# Mood-Badge.net
KiCad netlist of a schematic drawn in EAGLE
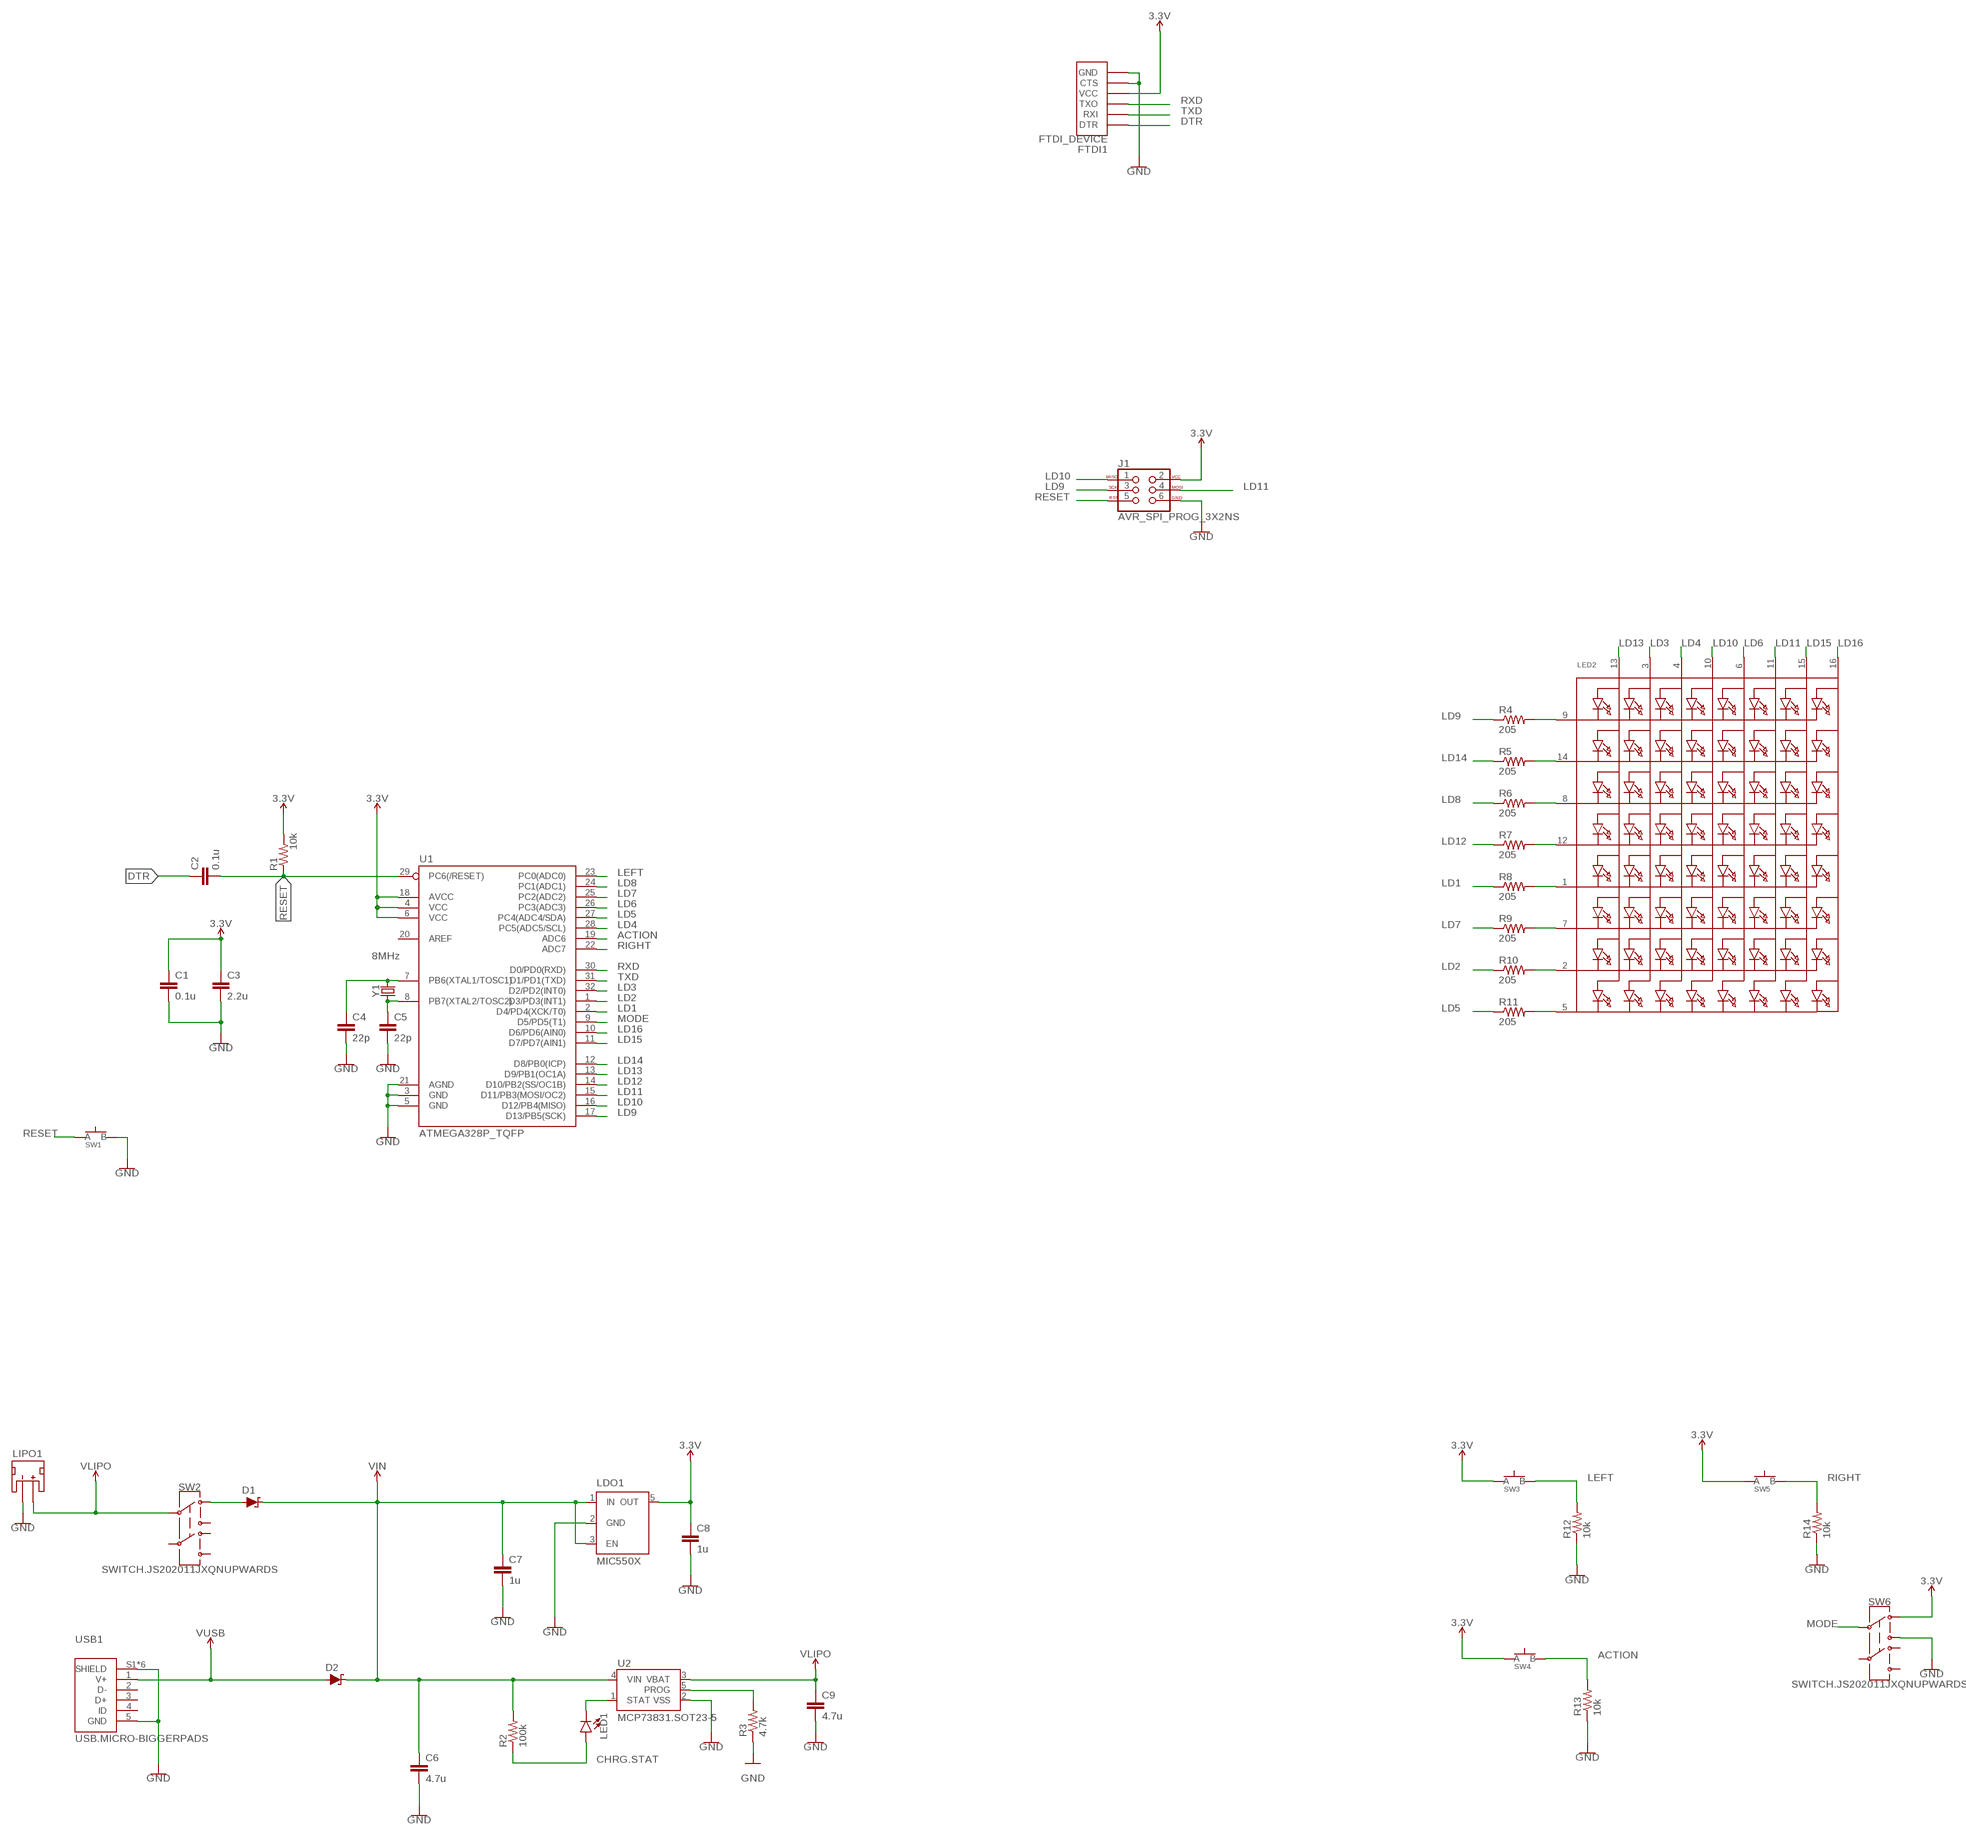
[diagram p0: schematic, sheet 1]

(export (version "E")
  (design (tool "Eeschema 10.0.6"))
  (components
    (comp (ref "C1")
      (value "0.1u")
      (footprint "eagle-import:C0603")
      (libsource (lib "eagle-import") (part "CAPACITOR0603"))
    )
    (comp (ref "C2")
      (value "0.1u")
      (footprint "eagle-import:C0603")
      (libsource (lib "eagle-import") (part "CAPACITOR0603"))
    )
    (comp (ref "C3")
      (value "2.2u")
      (footprint "eagle-import:C0603")
      (libsource (lib "eagle-import") (part "CAPACITOR0603"))
    )
    (comp (ref "C4")
      (value "22p")
      (footprint "eagle-import:C0603")
      (libsource (lib "eagle-import") (part "CAPACITOR0603"))
    )
    (comp (ref "C5")
      (value "22p")
      (footprint "eagle-import:C0603")
      (libsource (lib "eagle-import") (part "CAPACITOR0603"))
    )
    (comp (ref "C6")
      (value "4.7u")
      (footprint "eagle-import:C0603")
      (libsource (lib "eagle-import") (part "CAPACITOR0603"))
    )
    (comp (ref "C7")
      (value "1u")
      (footprint "eagle-import:C0603")
      (libsource (lib "eagle-import") (part "CAPACITOR0603"))
    )
    (comp (ref "C8")
      (value "1u")
      (footprint "eagle-import:C0603")
      (libsource (lib "eagle-import") (part "CAPACITOR0603"))
    )
    (comp (ref "C9")
      (value "4.7u")
      (footprint "eagle-import:C0603")
      (libsource (lib "eagle-import") (part "CAPACITOR0603"))
    )
    (comp (ref "D1")
      (value "SCHOTTKY-USC")
      (footprint "eagle-import:USC")
      (libsource (lib "eagle-import") (part "SCHOTTKY-USC"))
    )
    (comp (ref "D2")
      (value "SCHOTTKY-USC")
      (footprint "eagle-import:USC")
      (libsource (lib "eagle-import") (part "SCHOTTKY-USC"))
    )
    (comp (ref "FTDI1")
      (value "FTDI_DEVICE")
      (footprint "eagle-import:FTDI_DEVICE")
      (libsource (lib "eagle-import") (part "FTDI_DEVICE"))
    )
    (comp (ref "J1")
      (value "AVR_SPI_PROG_3X2NS")
      (footprint "eagle-import:2X3-NS")
      (libsource (lib "eagle-import") (part "AVR_SPI_PROG_3X2NS"))
    )
    (comp (ref "LDO1")
      (value "MIC550X")
      (footprint "eagle-import:SOT23-5")
      (libsource (lib "eagle-import") (part "MIC550X"))
    )
    (comp (ref "LED1")
      (value "LED0603")
      (footprint "eagle-import:LED-0603")
      (libsource (lib "eagle-import") (part "LED0603"))
    )
    (comp (ref "LED2")
      (value "DOTMATRIX_8X8_ROWCATHODEM12A881UR")
      (footprint "eagle-import:DOTMATRIX_BL-M12A881UR")
      (libsource (lib "eagle-import") (part "DOTMATRIX_8X8_ROWCATHODEM12A881UR"))
    )
    (comp (ref "LIPO1")
      (value "JST_2MM_MALE")
      (footprint "eagle-import:JST-2-SMD")
      (libsource (lib "eagle-import") (part "JST_2MM_MALE"))
    )
    (comp (ref "R1")
      (value "10k")
      (footprint "eagle-import:R0603")
      (libsource (lib "eagle-import") (part "RESISTOR0603"))
    )
    (comp (ref "R2")
      (value "100k")
      (footprint "eagle-import:R0603")
      (libsource (lib "eagle-import") (part "RESISTOR0603"))
    )
    (comp (ref "R3")
      (value "4.7k")
      (footprint "eagle-import:R0603")
      (libsource (lib "eagle-import") (part "RESISTOR0603"))
    )
    (comp (ref "R4")
      (value "205")
      (footprint "eagle-import:R0603")
      (libsource (lib "eagle-import") (part "RESISTOR0603"))
    )
    (comp (ref "R5")
      (value "205")
      (footprint "eagle-import:R0603")
      (libsource (lib "eagle-import") (part "RESISTOR0603"))
    )
    (comp (ref "R6")
      (value "205")
      (footprint "eagle-import:R0603")
      (libsource (lib "eagle-import") (part "RESISTOR0603"))
    )
    (comp (ref "R7")
      (value "205")
      (footprint "eagle-import:R0603")
      (libsource (lib "eagle-import") (part "RESISTOR0603"))
    )
    (comp (ref "R8")
      (value "205")
      (footprint "eagle-import:R0603")
      (libsource (lib "eagle-import") (part "RESISTOR0603"))
    )
    (comp (ref "R9")
      (value "205")
      (footprint "eagle-import:R0603")
      (libsource (lib "eagle-import") (part "RESISTOR0603"))
    )
    (comp (ref "R10")
      (value "205")
      (footprint "eagle-import:R0603")
      (libsource (lib "eagle-import") (part "RESISTOR0603"))
    )
    (comp (ref "R11")
      (value "205")
      (footprint "eagle-import:R0603")
      (libsource (lib "eagle-import") (part "RESISTOR0603"))
    )
    (comp (ref "R12")
      (value "10k")
      (footprint "eagle-import:R0603")
      (libsource (lib "eagle-import") (part "RESISTOR0603"))
    )
    (comp (ref "R13")
      (value "10k")
      (footprint "eagle-import:R0603")
      (libsource (lib "eagle-import") (part "RESISTOR0603"))
    )
    (comp (ref "R14")
      (value "10k")
      (footprint "eagle-import:R0603")
      (libsource (lib "eagle-import") (part "RESISTOR0603"))
    )
    (comp (ref "SW1")
      (value "SPST.KT11P4SM34LFS")
      (footprint "eagle-import:SPST.KT11P4SM34LFS")
      (libsource (lib "eagle-import") (part "SPST.KT11P4SM34LFS"))
    )
    (comp (ref "SW2")
      (value "SWITCH.JS202011JXQNUPWARDS")
      (footprint "eagle-import:SWITCH.00")
      (libsource (lib "eagle-import") (part "SWITCH.JS202011JXQNUPWARDS"))
    )
    (comp (ref "SW3")
      (value "SPST.KT11P4SM34LFS")
      (footprint "eagle-import:SPST.KT11P4SM34LFS")
      (libsource (lib "eagle-import") (part "SPST.KT11P4SM34LFS"))
    )
    (comp (ref "SW4")
      (value "SPST.KT11P4SM34LFS")
      (footprint "eagle-import:SPST.KT11P4SM34LFS")
      (libsource (lib "eagle-import") (part "SPST.KT11P4SM34LFS"))
    )
    (comp (ref "SW5")
      (value "SPST.KT11P4SM34LFS")
      (footprint "eagle-import:SPST.KT11P4SM34LFS")
      (libsource (lib "eagle-import") (part "SPST.KT11P4SM34LFS"))
    )
    (comp (ref "SW6")
      (value "SWITCH.JS202011JXQNUPWARDS")
      (footprint "eagle-import:SWITCH.00")
      (libsource (lib "eagle-import") (part "SWITCH.JS202011JXQNUPWARDS"))
    )
    (comp (ref "U1")
      (value "ATMEGA328P_TQFP")
      (footprint "eagle-import:TQFP32-08")
      (libsource (lib "eagle-import") (part "ATMEGA328P_TQFP"))
    )
    (comp (ref "U2")
      (value "MCP73831.SOT23-5")
      (footprint "eagle-import:SOT23-5")
      (libsource (lib "eagle-import") (part "MCP73831.SOT23-5"))
    )
    (comp (ref "USB1")
      (value "USB.MICRO-BIGGERPADS")
      (footprint "eagle-import:USB-MICRO-01.BIGGERPADS")
      (libsource (lib "eagle-import") (part "USB.MICRO-BIGGERPADS"))
    )
    (comp (ref "Y1")
      (value "8MHz")
      (footprint "eagle-import:CA-301")
      (libsource (lib "eagle-import") (part "CRYSTAL-CA-310"))
    )
  )
  (nets
    (net (code "1") (name "/ACTION") (class "Default")
      (node (ref "R13") (pin "2") (pinfunction "2_2") (pintype "passive"))
      (node (ref "SW4") (pin "3") (pinfunction "B_3") (pintype "bidirectional"))
      (node (ref "SW4") (pin "4") (pinfunction "B_4") (pintype "bidirectional"))
      (node (ref "U1") (pin "19") (pinfunction "ADC6_19") (pintype "bidirectional"))
    )
    (net (code "2") (name "/CHRG.STAT") (class "Default")
      (node (ref "LED1") (pin "A") (pinfunction "A_A") (pintype "passive"))
      (node (ref "R2") (pin "1") (pinfunction "1_1") (pintype "passive"))
    )
    (net (code "3") (name "/LD1") (class "Default")
      (node (ref "R8") (pin "1") (pinfunction "1_1") (pintype "passive"))
      (node (ref "U1") (pin "2") (pinfunction "D4/PD4(XCK/T0)_2") (pintype "bidirectional"))
    )
    (net (code "4") (name "/LD2") (class "Default")
      (node (ref "R10") (pin "1") (pinfunction "1_1") (pintype "passive"))
      (node (ref "U1") (pin "1") (pinfunction "D3/PD3(INT1)_1") (pintype "bidirectional"))
    )
    (net (code "5") (name "/LD3") (class "Default")
      (node (ref "LED2") (pin "3") (pinfunction "A2_3") (pintype "bidirectional"))
      (node (ref "U1") (pin "32") (pinfunction "D2/PD2(INT0)_32") (pintype "bidirectional"))
    )
    (net (code "6") (name "/LD4") (class "Default")
      (node (ref "LED2") (pin "4") (pinfunction "A3_4") (pintype "bidirectional"))
      (node (ref "U1") (pin "28") (pinfunction "PC5(ADC5/SCL)_28") (pintype "bidirectional"))
    )
    (net (code "7") (name "/LD5") (class "Default")
      (node (ref "R11") (pin "1") (pinfunction "1_1") (pintype "passive"))
      (node (ref "U1") (pin "27") (pinfunction "PC4(ADC4/SDA)_27") (pintype "bidirectional"))
    )
    (net (code "8") (name "/LD6") (class "Default")
      (node (ref "LED2") (pin "6") (pinfunction "A5_6") (pintype "bidirectional"))
      (node (ref "U1") (pin "26") (pinfunction "PC3(ADC3)_26") (pintype "bidirectional"))
    )
    (net (code "9") (name "/LD7") (class "Default")
      (node (ref "R9") (pin "1") (pinfunction "1_1") (pintype "passive"))
      (node (ref "U1") (pin "25") (pinfunction "PC2(ADC2)_25") (pintype "bidirectional"))
    )
    (net (code "10") (name "/LD8") (class "Default")
      (node (ref "R6") (pin "1") (pinfunction "1_1") (pintype "passive"))
      (node (ref "U1") (pin "24") (pinfunction "PC1(ADC1)_24") (pintype "bidirectional"))
    )
    (net (code "11") (name "/LD9") (class "Default")
      (node (ref "J1") (pin "3") (pinfunction "3_3") (pintype "passive"))
      (node (ref "R4") (pin "1") (pinfunction "1_1") (pintype "passive"))
      (node (ref "U1") (pin "17") (pinfunction "D13/PB5(SCK)_17") (pintype "bidirectional"))
    )
    (net (code "12") (name "/LD10") (class "Default")
      (node (ref "J1") (pin "1") (pinfunction "1_1") (pintype "passive"))
      (node (ref "LED2") (pin "10") (pinfunction "A4_10") (pintype "bidirectional"))
      (node (ref "U1") (pin "16") (pinfunction "D12/PB4(MISO)_16") (pintype "bidirectional"))
    )
    (net (code "13") (name "/LD11") (class "Default")
      (node (ref "J1") (pin "4") (pinfunction "4_4") (pintype "passive"))
      (node (ref "LED2") (pin "11") (pinfunction "A6_11") (pintype "bidirectional"))
      (node (ref "U1") (pin "15") (pinfunction "D11/PB3(MOSI/OC2)_15") (pintype "bidirectional"))
    )
    (net (code "14") (name "/LD12") (class "Default")
      (node (ref "R7") (pin "1") (pinfunction "1_1") (pintype "passive"))
      (node (ref "U1") (pin "14") (pinfunction "D10/PB2(SS/OC1B)_14") (pintype "bidirectional"))
    )
    (net (code "15") (name "/LD13") (class "Default")
      (node (ref "LED2") (pin "13") (pinfunction "A1_13") (pintype "bidirectional"))
      (node (ref "U1") (pin "13") (pinfunction "D9/PB1(OC1A)_13") (pintype "bidirectional"))
    )
    (net (code "16") (name "/LD14") (class "Default")
      (node (ref "R5") (pin "1") (pinfunction "1_1") (pintype "passive"))
      (node (ref "U1") (pin "12") (pinfunction "D8/PB0(ICP)_12") (pintype "bidirectional"))
    )
    (net (code "17") (name "/LD15") (class "Default")
      (node (ref "LED2") (pin "15") (pinfunction "A7_15") (pintype "bidirectional"))
      (node (ref "U1") (pin "11") (pinfunction "D7/PD7(AIN1)_11") (pintype "bidirectional"))
    )
    (net (code "18") (name "/LD16") (class "Default")
      (node (ref "LED2") (pin "16") (pinfunction "A8_16") (pintype "bidirectional"))
      (node (ref "U1") (pin "10") (pinfunction "D6/PD6(AIN0)_10") (pintype "bidirectional"))
    )
    (net (code "19") (name "/LEFT") (class "Default")
      (node (ref "R12") (pin "2") (pinfunction "2_2") (pintype "passive"))
      (node (ref "SW3") (pin "3") (pinfunction "B_3") (pintype "bidirectional"))
      (node (ref "SW3") (pin "4") (pinfunction "B_4") (pintype "bidirectional"))
      (node (ref "U1") (pin "23") (pinfunction "PC0(ADC0)_23") (pintype "bidirectional"))
    )
    (net (code "20") (name "/MODE") (class "Default")
      (node (ref "SW6") (pin "2") (pinfunction "2_2") (pintype "bidirectional"))
      (node (ref "U1") (pin "9") (pinfunction "D5/PD5(T1)_9") (pintype "bidirectional"))
    )
    (net (code "21") (name "/RIGHT") (class "Default")
      (node (ref "R14") (pin "2") (pinfunction "2_2") (pintype "passive"))
      (node (ref "SW5") (pin "3") (pinfunction "B_3") (pintype "bidirectional"))
      (node (ref "SW5") (pin "4") (pinfunction "B_4") (pintype "bidirectional"))
      (node (ref "U1") (pin "22") (pinfunction "ADC7_22") (pintype "bidirectional"))
    )
    (net (code "22") (name "/RXD") (class "Default")
      (node (ref "FTDI1") (pin "RXI") (pinfunction "TXO_RXI") (pintype "bidirectional"))
      (node (ref "U1") (pin "30") (pinfunction "D0/PD0(RXD)_30") (pintype "bidirectional"))
    )
    (net (code "23") (name "/TXD") (class "Default")
      (node (ref "FTDI1") (pin "TXO") (pinfunction "RXI_TXO") (pintype "bidirectional"))
      (node (ref "U1") (pin "31") (pinfunction "D1/PD1(TXD)_31") (pintype "bidirectional"))
    )
    (net (code "24") (name "3.3V") (class "Default")
      (node (ref "C1") (pin "1") (pinfunction "1_1") (pintype "passive"))
      (node (ref "C3") (pin "1") (pinfunction "1_1") (pintype "passive"))
      (node (ref "C8") (pin "1") (pinfunction "1_1") (pintype "passive"))
      (node (ref "FTDI1") (pin "VCC") (pinfunction "VCC_VCC") (pintype "bidirectional"))
      (node (ref "J1") (pin "2") (pinfunction "2_2") (pintype "passive"))
      (node (ref "LDO1") (pin "5") (pinfunction "OUT_5") (pintype "bidirectional"))
      (node (ref "R1") (pin "2") (pinfunction "2_2") (pintype "passive"))
      (node (ref "SW3") (pin "1") (pinfunction "A_1") (pintype "bidirectional"))
      (node (ref "SW3") (pin "2") (pinfunction "A_2") (pintype "bidirectional"))
      (node (ref "SW4") (pin "1") (pinfunction "A_1") (pintype "bidirectional"))
      (node (ref "SW4") (pin "2") (pinfunction "A_2") (pintype "bidirectional"))
      (node (ref "SW5") (pin "1") (pinfunction "A_1") (pintype "bidirectional"))
      (node (ref "SW5") (pin "2") (pinfunction "A_2") (pintype "bidirectional"))
      (node (ref "SW6") (pin "1") (pinfunction "1_1") (pintype "bidirectional"))
      (node (ref "U1") (pin "18") (pinfunction "AVCC_18") (pintype "bidirectional"))
      (node (ref "U1") (pin "4") (pinfunction "VCC_4") (pintype "bidirectional"))
      (node (ref "U1") (pin "6") (pinfunction "VCC_6") (pintype "bidirectional"))
    )
    (net (code "25") (name "DTR") (class "Default")
      (node (ref "C2") (pin "1") (pinfunction "1_1") (pintype "passive"))
      (node (ref "FTDI1") (pin "DTR") (pinfunction "DTR_DTR") (pintype "bidirectional"))
    )
    (net (code "26") (name "GND") (class "Default")
      (node (ref "C1") (pin "2") (pinfunction "2_2") (pintype "passive"))
      (node (ref "C3") (pin "2") (pinfunction "2_2") (pintype "passive"))
      (node (ref "C4") (pin "2") (pinfunction "2_2") (pintype "passive"))
      (node (ref "C5") (pin "2") (pinfunction "2_2") (pintype "passive"))
      (node (ref "C6") (pin "2") (pinfunction "2_2") (pintype "passive"))
      (node (ref "C7") (pin "2") (pinfunction "2_2") (pintype "passive"))
      (node (ref "C8") (pin "2") (pinfunction "2_2") (pintype "passive"))
      (node (ref "C9") (pin "2") (pinfunction "2_2") (pintype "passive"))
      (node (ref "FTDI1") (pin "CTS") (pinfunction "CTS_CTS") (pintype "bidirectional"))
      (node (ref "FTDI1") (pin "GND") (pinfunction "GND_GND") (pintype "bidirectional"))
      (node (ref "J1") (pin "6") (pinfunction "6_6") (pintype "passive"))
      (node (ref "LDO1") (pin "2") (pinfunction "GND_2") (pintype "bidirectional"))
      (node (ref "LIPO1") (pin "1") (pinfunction "-_1") (pintype "bidirectional"))
      (node (ref "R12") (pin "1") (pinfunction "1_1") (pintype "passive"))
      (node (ref "R13") (pin "1") (pinfunction "1_1") (pintype "passive"))
      (node (ref "R14") (pin "1") (pinfunction "1_1") (pintype "passive"))
      (node (ref "R3") (pin "1") (pinfunction "1_1") (pintype "passive"))
      (node (ref "SW1") (pin "3") (pinfunction "B_3") (pintype "bidirectional"))
      (node (ref "SW1") (pin "4") (pinfunction "B_4") (pintype "bidirectional"))
      (node (ref "SW6") (pin "3") (pinfunction "3_3") (pintype "bidirectional"))
      (node (ref "U1") (pin "21") (pinfunction "AGND_21") (pintype "bidirectional"))
      (node (ref "U1") (pin "3") (pinfunction "GND_3") (pintype "bidirectional"))
      (node (ref "U1") (pin "5") (pinfunction "GND_5") (pintype "bidirectional"))
      (node (ref "U2") (pin "2") (pinfunction "VSS_2") (pintype "power_in"))
      (node (ref "USB1") (pin "5") (pinfunction "GND_5") (pintype "bidirectional"))
      (node (ref "USB1") (pin "S1") (pinfunction "SHIELD_S1") (pintype "bidirectional"))
      (node (ref "USB1") (pin "S2") (pinfunction "SHIELD_S2") (pintype "bidirectional"))
      (node (ref "USB1") (pin "S3") (pinfunction "SHIELD_S3") (pintype "bidirectional"))
      (node (ref "USB1") (pin "S4") (pinfunction "SHIELD_S4") (pintype "bidirectional"))
      (node (ref "USB1") (pin "S5") (pinfunction "SHIELD_S5") (pintype "bidirectional"))
      (node (ref "USB1") (pin "S6") (pinfunction "SHIELD_S6") (pintype "bidirectional"))
    )
    (net (code "27") (name "Net-(D1-A)") (class "Default")
      (node (ref "D1") (pin "+") (pinfunction "A_+") (pintype "passive"))
      (node (ref "SW2") (pin "1") (pinfunction "1_1") (pintype "bidirectional"))
    )
    (net (code "28") (name "Net-(LED2-K1)") (class "Default")
      (node (ref "LED2") (pin "9") (pinfunction "K1_9") (pintype "bidirectional"))
      (node (ref "R4") (pin "2") (pinfunction "2_2") (pintype "passive"))
    )
    (net (code "29") (name "Net-(LED2-K2)") (class "Default")
      (node (ref "LED2") (pin "14") (pinfunction "K2_14") (pintype "bidirectional"))
      (node (ref "R5") (pin "2") (pinfunction "2_2") (pintype "passive"))
    )
    (net (code "30") (name "Net-(LED2-K3)") (class "Default")
      (node (ref "LED2") (pin "8") (pinfunction "K3_8") (pintype "bidirectional"))
      (node (ref "R6") (pin "2") (pinfunction "2_2") (pintype "passive"))
    )
    (net (code "31") (name "Net-(LED2-K4)") (class "Default")
      (node (ref "LED2") (pin "12") (pinfunction "K4_12") (pintype "bidirectional"))
      (node (ref "R7") (pin "2") (pinfunction "2_2") (pintype "passive"))
    )
    (net (code "32") (name "Net-(LED2-K5)") (class "Default")
      (node (ref "LED2") (pin "1") (pinfunction "K5_1") (pintype "bidirectional"))
      (node (ref "R8") (pin "2") (pinfunction "2_2") (pintype "passive"))
    )
    (net (code "33") (name "Net-(LED2-K6)") (class "Default")
      (node (ref "LED2") (pin "7") (pinfunction "K6_7") (pintype "bidirectional"))
      (node (ref "R9") (pin "2") (pinfunction "2_2") (pintype "passive"))
    )
    (net (code "34") (name "Net-(LED2-K7)") (class "Default")
      (node (ref "LED2") (pin "2") (pinfunction "K7_2") (pintype "bidirectional"))
      (node (ref "R10") (pin "2") (pinfunction "2_2") (pintype "passive"))
    )
    (net (code "35") (name "Net-(LED2-K8)") (class "Default")
      (node (ref "LED2") (pin "5") (pinfunction "K8_5") (pintype "bidirectional"))
      (node (ref "R11") (pin "2") (pinfunction "2_2") (pintype "passive"))
    )
    (net (code "36") (name "Net-(U1-PB6(XTAL1{slash}TOSC1))") (class "Default")
      (node (ref "C4") (pin "1") (pinfunction "1_1") (pintype "passive"))
      (node (ref "U1") (pin "7") (pinfunction "PB6(XTAL1/TOSC1)_7") (pintype "bidirectional"))
      (node (ref "Y1") (pin "2") (pinfunction "2_2") (pintype "passive"))
    )
    (net (code "37") (name "Net-(U1-PB7(XTAL2{slash}TOSC2))") (class "Default")
      (node (ref "C5") (pin "1") (pinfunction "1_1") (pintype "passive"))
      (node (ref "U1") (pin "8") (pinfunction "PB7(XTAL2/TOSC2)_8") (pintype "bidirectional"))
      (node (ref "Y1") (pin "1") (pinfunction "1_1") (pintype "passive"))
    )
    (net (code "38") (name "Net-(U2-PROG)") (class "Default")
      (node (ref "R3") (pin "2") (pinfunction "2_2") (pintype "passive"))
      (node (ref "U2") (pin "5") (pinfunction "PROG_5") (pintype "input"))
    )
    (net (code "39") (name "Net-(U2-STAT)") (class "Default")
      (node (ref "LED1") (pin "C") (pinfunction "C_C") (pintype "passive"))
      (node (ref "U2") (pin "1") (pinfunction "STAT_1") (pintype "output"))
    )
    (net (code "40") (name "RESET") (class "Default")
      (node (ref "C2") (pin "2") (pinfunction "2_2") (pintype "passive"))
      (node (ref "J1") (pin "5") (pinfunction "5_5") (pintype "passive"))
      (node (ref "R1") (pin "1") (pinfunction "1_1") (pintype "passive"))
      (node (ref "SW1") (pin "1") (pinfunction "A_1") (pintype "bidirectional"))
      (node (ref "SW1") (pin "2") (pinfunction "A_2") (pintype "bidirectional"))
      (node (ref "U1") (pin "29") (pinfunction "PC6(/RESET)_29") (pintype "bidirectional"))
    )
    (net (code "41") (name "VIN") (class "Default")
      (node (ref "C6") (pin "1") (pinfunction "1_1") (pintype "passive"))
      (node (ref "C7") (pin "1") (pinfunction "1_1") (pintype "passive"))
      (node (ref "D1") (pin "-") (pinfunction "C_-") (pintype "passive"))
      (node (ref "D2") (pin "-") (pinfunction "C_-") (pintype "passive"))
      (node (ref "LDO1") (pin "1") (pinfunction "IN_1") (pintype "bidirectional"))
      (node (ref "LDO1") (pin "3") (pinfunction "EN_3") (pintype "bidirectional"))
      (node (ref "R2") (pin "2") (pinfunction "2_2") (pintype "passive"))
      (node (ref "U2") (pin "4") (pinfunction "VIN_4") (pintype "power_in"))
    )
    (net (code "42") (name "VLIPO") (class "Default")
      (node (ref "C9") (pin "1") (pinfunction "1_1") (pintype "passive"))
      (node (ref "LIPO1") (pin "2") (pinfunction "+_2") (pintype "bidirectional"))
      (node (ref "SW2") (pin "2") (pinfunction "2_2") (pintype "bidirectional"))
      (node (ref "U2") (pin "3") (pinfunction "VBAT_3") (pintype "power_in"))
    )
    (net (code "43") (name "VUSB") (class "Default")
      (node (ref "D2") (pin "+") (pinfunction "A_+") (pintype "passive"))
      (node (ref "USB1") (pin "1") (pinfunction "V+_1") (pintype "bidirectional"))
    )
    (net (code "44") (name "unconnected-(LIPO1-PAD1-PadNC1)") (class "Default")
      (node (ref "LIPO1") (pin "NC1") (pinfunction "PAD1_NC1") (pintype "bidirectional"))
    )
    (net (code "45") (name "unconnected-(LIPO1-PAD2-PadNC2)") (class "Default")
      (node (ref "LIPO1") (pin "NC2") (pinfunction "PAD2_NC2") (pintype "bidirectional"))
    )
    (net (code "46") (name "unconnected-(SW2-4-Pad5)") (class "Default")
      (node (ref "SW2") (pin "5") (pinfunction "4_5") (pintype "bidirectional"))
    )
    (net (code "47") (name "unconnected-(SW2-5-Pad6)") (class "Default")
      (node (ref "SW2") (pin "6") (pinfunction "5_6") (pintype "bidirectional"))
    )
    (net (code "48") (name "unconnected-(SW2-6-Pad7)") (class "Default")
      (node (ref "SW2") (pin "7") (pinfunction "6_7") (pintype "bidirectional"))
    )
    (net (code "49") (name "unconnected-(SW2-Pad3)") (class "Default")
      (node (ref "SW2") (pin "3") (pinfunction "3_3") (pintype "bidirectional"))
    )
    (net (code "50") (name "unconnected-(SW6-4-Pad5)") (class "Default")
      (node (ref "SW6") (pin "5") (pinfunction "4_5") (pintype "bidirectional"))
    )
    (net (code "51") (name "unconnected-(SW6-5-Pad6)") (class "Default")
      (node (ref "SW6") (pin "6") (pinfunction "5_6") (pintype "bidirectional"))
    )
    (net (code "52") (name "unconnected-(SW6-6-Pad7)") (class "Default")
      (node (ref "SW6") (pin "7") (pinfunction "6_7") (pintype "bidirectional"))
    )
    (net (code "53") (name "unconnected-(U1-AREF-Pad20)") (class "Default")
      (node (ref "U1") (pin "20") (pinfunction "AREF_20") (pintype "bidirectional"))
    )
    (net (code "54") (name "unconnected-(USB1-D+-Pad3)") (class "Default")
      (node (ref "USB1") (pin "3") (pinfunction "D+_3") (pintype "bidirectional"))
    )
    (net (code "55") (name "unconnected-(USB1-D--Pad2)") (class "Default")
      (node (ref "USB1") (pin "2") (pinfunction "D-_2") (pintype "bidirectional"))
    )
    (net (code "56") (name "unconnected-(USB1-ID-Pad4)") (class "Default")
      (node (ref "USB1") (pin "4") (pinfunction "ID_4") (pintype "bidirectional"))
    )
  )
)
